# OpAmp.net
KiCad netlist of a schematic drawn in Altium Designer
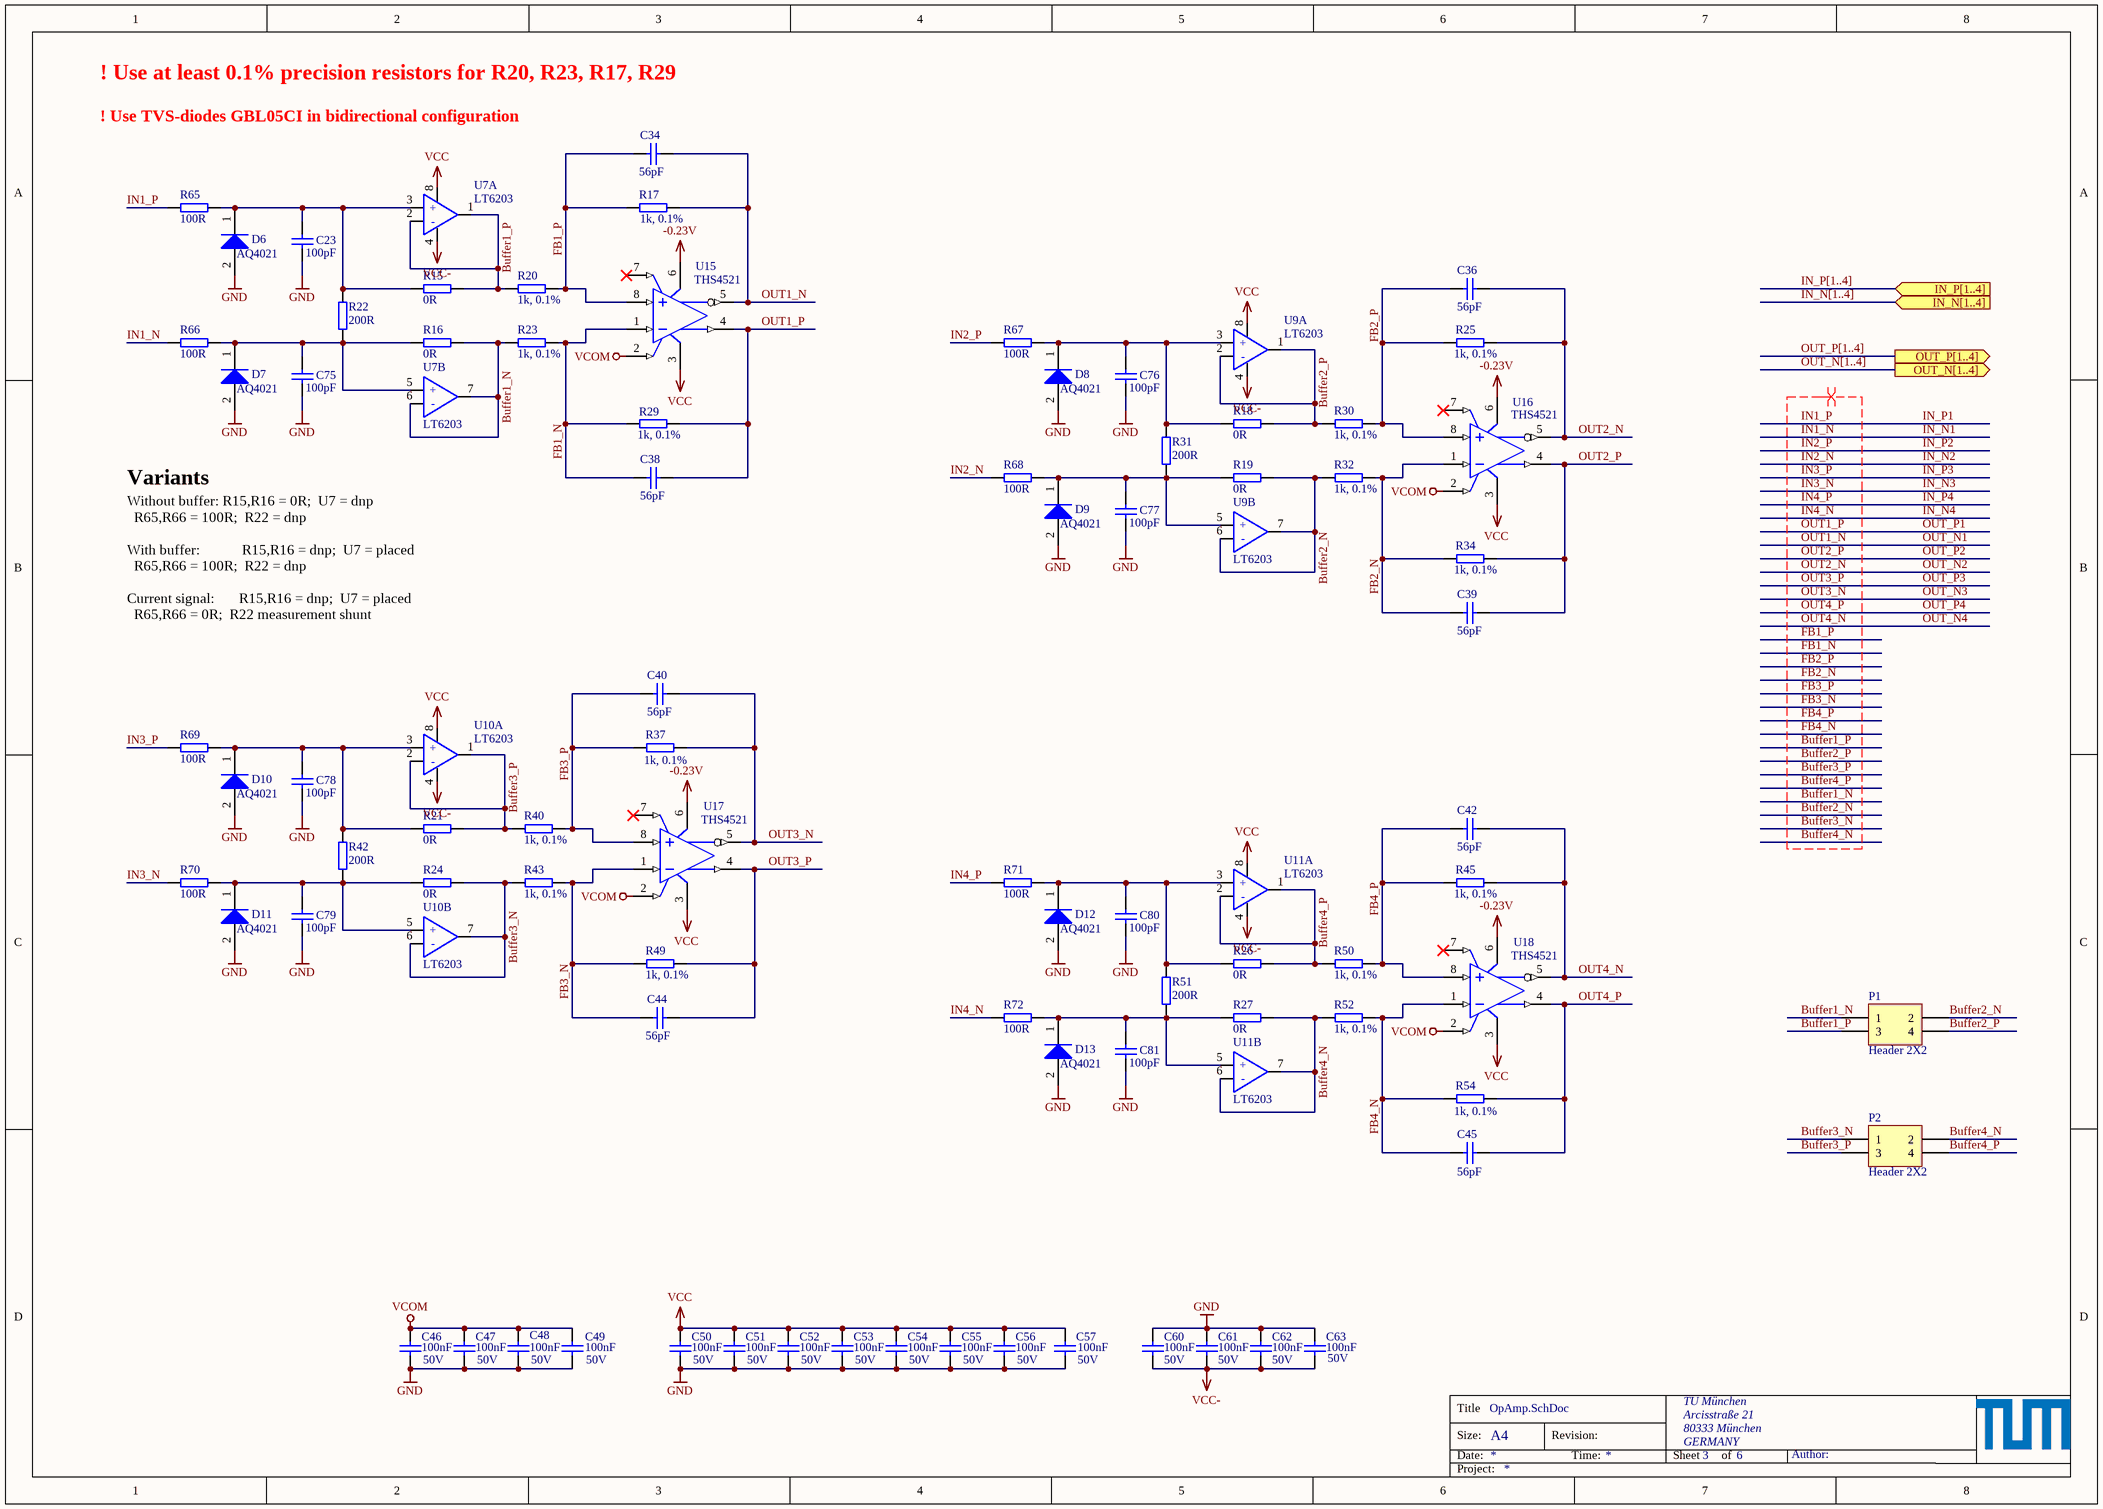
[diagram p0: OpAmp.SchDoc]

(export (version "E")
  (design (tool "Eeschema 10.0.6"))
  (components
    (comp (ref "C23")
      (value "100pF")
      (footprint "CAPC1608X07N")
      (fields
        (field (name "MF") "Würth Elektronik")
        (field (name "MPN") "885012006057")
        (field (name "VOLTAGE") "50V")
      )
      (libsource (lib "UltraZohm_ADC") (part "Cap_0603"))
    )
    (comp (ref "C34")
      (value "56pF")
      (footprint "CAPC1608X07N")
      (fields
        (field (name "MF") "Vishay")
        (field (name "MPN") "VJ0603A560JXACW1BC")
        (field (name "VOLTAGE") "50V")
      )
      (libsource (lib "UltraZohm_ADC") (part "Cap_0603"))
    )
    (comp (ref "C36")
      (value "56pF")
      (footprint "CAPC1608X07N")
      (fields
        (field (name "MF") "Vishay")
        (field (name "MPN") "VJ0603A560JXACW1BC")
        (field (name "VOLTAGE") "50V")
      )
      (libsource (lib "UltraZohm_ADC") (part "Cap_0603"))
    )
    (comp (ref "C38")
      (value "56pF")
      (footprint "CAPC1608X07N")
      (fields
        (field (name "MF") "Vishay")
        (field (name "MPN") "VJ0603A560JXACW1BC")
        (field (name "VOLTAGE") "50V")
      )
      (libsource (lib "UltraZohm_ADC") (part "Cap_0603"))
    )
    (comp (ref "C39")
      (value "56pF")
      (footprint "CAPC1608X07N")
      (fields
        (field (name "MF") "Vishay")
        (field (name "MPN") "VJ0603A560JXACW1BC")
        (field (name "VOLTAGE") "50V")
      )
      (libsource (lib "UltraZohm_ADC") (part "Cap_0603"))
    )
    (comp (ref "C40")
      (value "56pF")
      (footprint "CAPC1608X07N")
      (fields
        (field (name "MF") "Vishay")
        (field (name "MPN") "VJ0603A560JXACW1BC")
        (field (name "VOLTAGE") "50V")
      )
      (libsource (lib "UltraZohm_ADC") (part "Cap_0603"))
    )
    (comp (ref "C42")
      (value "56pF")
      (footprint "CAPC1608X07N")
      (fields
        (field (name "MF") "Vishay")
        (field (name "MPN") "VJ0603A560JXACW1BC")
        (field (name "VOLTAGE") "50V")
      )
      (libsource (lib "UltraZohm_ADC") (part "Cap_0603"))
    )
    (comp (ref "C44")
      (value "56pF")
      (footprint "CAPC1608X07N")
      (fields
        (field (name "MF") "Vishay")
        (field (name "MPN") "VJ0603A560JXACW1BC")
        (field (name "VOLTAGE") "50V")
      )
      (libsource (lib "UltraZohm_ADC") (part "Cap_0603"))
    )
    (comp (ref "C45")
      (value "56pF")
      (footprint "CAPC1608X07N")
      (fields
        (field (name "MF") "Vishay")
        (field (name "MPN") "VJ0603A560JXACW1BC")
        (field (name "VOLTAGE") "50V")
      )
      (libsource (lib "UltraZohm_ADC") (part "Cap_0603"))
    )
    (comp (ref "C46")
      (value "100nF")
      (footprint "CAPC1608X07N")
      (fields
        (field (name "MF") "Yageo")
        (field (name "MPN") "CC0603KRX7R9BB104")
        (field (name "VOLTAGE") "50V")
      )
      (libsource (lib "UltraZohm_ADC") (part "Cap_0603"))
    )
    (comp (ref "C47")
      (value "100nF")
      (footprint "CAPC1608X07N")
      (fields
        (field (name "MF") "Yageo")
        (field (name "MPN") "CC0603KRX7R9BB104")
        (field (name "VOLTAGE") "50V")
      )
      (libsource (lib "UltraZohm_ADC") (part "Cap_0603"))
    )
    (comp (ref "C48")
      (value "100nF")
      (footprint "CAPC1608X07N")
      (fields
        (field (name "MF") "Yageo")
        (field (name "MPN") "CC0603KRX7R9BB104")
        (field (name "VOLTAGE") "50V")
      )
      (libsource (lib "UltraZohm_ADC") (part "Cap_0603"))
    )
    (comp (ref "C49")
      (value "100nF")
      (footprint "CAPC1608X07N")
      (fields
        (field (name "MF") "Yageo")
        (field (name "MPN") "CC0603KRX7R9BB104")
        (field (name "VOLTAGE") "50V")
      )
      (libsource (lib "UltraZohm_ADC") (part "Cap_0603"))
    )
    (comp (ref "C50")
      (value "100nF")
      (footprint "CAPC1608X07N")
      (fields
        (field (name "MF") "Yageo")
        (field (name "MPN") "CC0603KRX7R9BB104")
        (field (name "VOLTAGE") "50V")
      )
      (libsource (lib "UltraZohm_ADC") (part "Cap_0603"))
    )
    (comp (ref "C51")
      (value "100nF")
      (footprint "CAPC1608X07N")
      (fields
        (field (name "MF") "Yageo")
        (field (name "MPN") "CC0603KRX7R9BB104")
        (field (name "VOLTAGE") "50V")
      )
      (libsource (lib "UltraZohm_ADC") (part "Cap_0603"))
    )
    (comp (ref "C52")
      (value "100nF")
      (footprint "CAPC1608X07N")
      (fields
        (field (name "MF") "Yageo")
        (field (name "MPN") "CC0603KRX7R9BB104")
        (field (name "VOLTAGE") "50V")
      )
      (libsource (lib "UltraZohm_ADC") (part "Cap_0603"))
    )
    (comp (ref "C53")
      (value "100nF")
      (footprint "CAPC1608X07N")
      (fields
        (field (name "MF") "Yageo")
        (field (name "MPN") "CC0603KRX7R9BB104")
        (field (name "VOLTAGE") "50V")
      )
      (libsource (lib "UltraZohm_ADC") (part "Cap_0603"))
    )
    (comp (ref "C54")
      (value "100nF")
      (footprint "CAPC1608X07N")
      (fields
        (field (name "MF") "Yageo")
        (field (name "MPN") "CC0603KRX7R9BB104")
        (field (name "VOLTAGE") "50V")
      )
      (libsource (lib "UltraZohm_ADC") (part "Cap_0603"))
    )
    (comp (ref "C55")
      (value "100nF")
      (footprint "CAPC1608X07N")
      (fields
        (field (name "MF") "Yageo")
        (field (name "MPN") "CC0603KRX7R9BB104")
        (field (name "VOLTAGE") "50V")
      )
      (libsource (lib "UltraZohm_ADC") (part "Cap_0603"))
    )
    (comp (ref "C56")
      (value "100nF")
      (footprint "CAPC1608X07N")
      (fields
        (field (name "MF") "Yageo")
        (field (name "MPN") "CC0603KRX7R9BB104")
        (field (name "VOLTAGE") "50V")
      )
      (libsource (lib "UltraZohm_ADC") (part "Cap_0603"))
    )
    (comp (ref "C57")
      (value "100nF")
      (footprint "CAPC1608X07N")
      (fields
        (field (name "MF") "Yageo")
        (field (name "MPN") "CC0603KRX7R9BB104")
        (field (name "VOLTAGE") "50V")
      )
      (libsource (lib "UltraZohm_ADC") (part "Cap_0603"))
    )
    (comp (ref "C60")
      (value "100nF")
      (footprint "CAPC1608X07N")
      (fields
        (field (name "MF") "Yageo")
        (field (name "MPN") "CC0603KRX7R9BB104")
        (field (name "VOLTAGE") "50V")
      )
      (libsource (lib "UltraZohm_ADC") (part "Cap_0603"))
    )
    (comp (ref "C61")
      (value "100nF")
      (footprint "CAPC1608X07N")
      (fields
        (field (name "MF") "Yageo")
        (field (name "MPN") "CC0603KRX7R9BB104")
        (field (name "VOLTAGE") "50V")
      )
      (libsource (lib "UltraZohm_ADC") (part "Cap_0603"))
    )
    (comp (ref "C62")
      (value "100nF")
      (footprint "CAPC1608X07N")
      (fields
        (field (name "MF") "Yageo")
        (field (name "MPN") "CC0603KRX7R9BB104")
        (field (name "VOLTAGE") "50V")
      )
      (libsource (lib "UltraZohm_ADC") (part "Cap_0603"))
    )
    (comp (ref "C63")
      (value "100nF")
      (footprint "CAPC1608X07N")
      (fields
        (field (name "MF") "Yageo")
        (field (name "MPN") "CC0603KRX7R9BB104")
        (field (name "VOLTAGE") "50V")
      )
      (libsource (lib "UltraZohm_ADC") (part "Cap_0603"))
    )
    (comp (ref "C75")
      (value "100pF")
      (footprint "CAPC1608X07N")
      (fields
        (field (name "MF") "Würth Elektronik")
        (field (name "MPN") "885012006057")
        (field (name "VOLTAGE") "50V")
      )
      (libsource (lib "UltraZohm_ADC") (part "Cap_0603"))
    )
    (comp (ref "C76")
      (value "100pF")
      (footprint "CAPC1608X07N")
      (fields
        (field (name "MF") "Würth Elektronik")
        (field (name "MPN") "885012006057")
        (field (name "VOLTAGE") "50V")
      )
      (libsource (lib "UltraZohm_ADC") (part "Cap_0603"))
    )
    (comp (ref "C77")
      (value "100pF")
      (footprint "CAPC1608X07N")
      (fields
        (field (name "MF") "Würth Elektronik")
        (field (name "MPN") "885012006057")
        (field (name "VOLTAGE") "50V")
      )
      (libsource (lib "UltraZohm_ADC") (part "Cap_0603"))
    )
    (comp (ref "C78")
      (value "100pF")
      (footprint "CAPC1608X07N")
      (fields
        (field (name "MF") "Würth Elektronik")
        (field (name "MPN") "885012006057")
        (field (name "VOLTAGE") "50V")
      )
      (libsource (lib "UltraZohm_ADC") (part "Cap_0603"))
    )
    (comp (ref "C79")
      (value "100pF")
      (footprint "CAPC1608X07N")
      (fields
        (field (name "MF") "Würth Elektronik")
        (field (name "MPN") "885012006057")
        (field (name "VOLTAGE") "50V")
      )
      (libsource (lib "UltraZohm_ADC") (part "Cap_0603"))
    )
    (comp (ref "C80")
      (value "100pF")
      (footprint "CAPC1608X07N")
      (fields
        (field (name "MF") "Würth Elektronik")
        (field (name "MPN") "885012006057")
        (field (name "VOLTAGE") "50V")
      )
      (libsource (lib "UltraZohm_ADC") (part "Cap_0603"))
    )
    (comp (ref "C81")
      (value "100pF")
      (footprint "CAPC1608X07N")
      (fields
        (field (name "MF") "Würth Elektronik")
        (field (name "MPN") "885012006057")
        (field (name "VOLTAGE") "50V")
      )
      (libsource (lib "UltraZohm_ADC") (part "Cap_0603"))
    )
    (comp (ref "D6")
      (value "AQ4021")
      (footprint "SOD-323_SuppressorDiode")
      (description "ESD Suppressor Diode TVS Bi-Dir 5V")
      (fields (field (name "MF") "Littelfuse") (field (name "MPN") "AQ4021-01FTG-C"))
      (libsource (lib "UltraZohm_ADC") (part "GBLCxx"))
    )
    (comp (ref "D7")
      (value "AQ4021")
      (footprint "SOD-323_SuppressorDiode")
      (description "ESD Suppressor Diode TVS Bi-Dir 5V")
      (fields (field (name "MF") "Littelfuse") (field (name "MPN") "AQ4021-01FTG-C"))
      (libsource (lib "UltraZohm_ADC") (part "GBLCxx"))
    )
    (comp (ref "D8")
      (value "AQ4021")
      (footprint "SOD-323_SuppressorDiode")
      (description "ESD Suppressor Diode TVS Bi-Dir 5V")
      (fields (field (name "MF") "Littelfuse") (field (name "MPN") "AQ4021-01FTG-C"))
      (libsource (lib "UltraZohm_ADC") (part "GBLCxx"))
    )
    (comp (ref "D9")
      (value "AQ4021")
      (footprint "SOD-323_SuppressorDiode")
      (description "ESD Suppressor Diode TVS Bi-Dir 5V")
      (fields (field (name "MF") "Littelfuse") (field (name "MPN") "AQ4021-01FTG-C"))
      (libsource (lib "UltraZohm_ADC") (part "GBLCxx"))
    )
    (comp (ref "D10")
      (value "AQ4021")
      (footprint "SOD-323_SuppressorDiode")
      (description "ESD Suppressor Diode TVS Bi-Dir 5V")
      (fields (field (name "MF") "Littelfuse") (field (name "MPN") "AQ4021-01FTG-C"))
      (libsource (lib "UltraZohm_ADC") (part "GBLCxx"))
    )
    (comp (ref "D11")
      (value "AQ4021")
      (footprint "SOD-323_SuppressorDiode")
      (description "ESD Suppressor Diode TVS Bi-Dir 5V")
      (fields (field (name "MF") "Littelfuse") (field (name "MPN") "AQ4021-01FTG-C"))
      (libsource (lib "UltraZohm_ADC") (part "GBLCxx"))
    )
    (comp (ref "D12")
      (value "AQ4021")
      (footprint "SOD-323_SuppressorDiode")
      (description "ESD Suppressor Diode TVS Bi-Dir 5V")
      (fields (field (name "MF") "Littelfuse") (field (name "MPN") "AQ4021-01FTG-C"))
      (libsource (lib "UltraZohm_ADC") (part "GBLCxx"))
    )
    (comp (ref "D13")
      (value "AQ4021")
      (footprint "SOD-323_SuppressorDiode")
      (description "ESD Suppressor Diode TVS Bi-Dir 5V")
      (fields (field (name "MF") "Littelfuse") (field (name "MPN") "AQ4021-01FTG-C"))
      (libsource (lib "UltraZohm_ADC") (part "GBLCxx"))
    )
    (comp (ref "P1")
      (value "Header 2X2")
      (footprint "HDR2X2")
      (description "Header, 2-Pin, Dual row")
      (fields (field (name "PUBLISHER") "Altium Limited"))
      (libsource (lib "Miscellaneous Connectors") (part "Header 2X2"))
    )
    (comp (ref "P2")
      (value "Header 2X2")
      (footprint "HDR2X2")
      (description "Header, 2-Pin, Dual row")
      (fields (field (name "PUBLISHER") "Altium Limited"))
      (libsource (lib "Miscellaneous Connectors") (part "Header 2X2"))
    )
    (comp (ref "R15")
      (value "0R")
      (footprint "RESC1608X06N")
      (fields (field (name "MF") "Vishay / Dale") (field (name "MPN") "CRCW06030000Z0EBC"))
      (libsource (lib "UltraZohm_ADC") (part "R_0603"))
    )
    (comp (ref "R16")
      (value "0R")
      (footprint "RESC1608X06N")
      (fields (field (name "MF") "Vishay / Dale") (field (name "MPN") "CRCW06030000Z0EBC"))
      (libsource (lib "UltraZohm_ADC") (part "R_0603"))
    )
    (comp (ref "R17")
      (value "1k, 0.1%")
      (footprint "RESC1608X06N")
      (description "Precision Resistor 1k 0.1% 0603")
      (fields (field (name "MF") "IRC/TT Electronics") (field (name "MPN") "PCF-W0603LF-03-1001-B-P-LT"))
      (libsource (lib "UltraZohm_ADC") (part "R_0603"))
    )
    (comp (ref "R18")
      (value "0R")
      (footprint "RESC1608X06N")
      (fields (field (name "MF") "Vishay / Dale") (field (name "MPN") "CRCW06030000Z0EBC"))
      (libsource (lib "UltraZohm_ADC") (part "R_0603"))
    )
    (comp (ref "R19")
      (value "0R")
      (footprint "RESC1608X06N")
      (fields (field (name "MF") "Vishay / Dale") (field (name "MPN") "CRCW06030000Z0EBC"))
      (libsource (lib "UltraZohm_ADC") (part "R_0603"))
    )
    (comp (ref "R20")
      (value "1k, 0.1%")
      (footprint "RESC1608X06N")
      (description "Precision Resistor 1k 0.1% 0603")
      (fields (field (name "MF") "IRC/TT Electronics") (field (name "MPN") "PCF-W0603LF-03-1001-B-P-LT"))
      (libsource (lib "UltraZohm_ADC") (part "R_0603"))
    )
    (comp (ref "R21")
      (value "0R")
      (footprint "RESC1608X06N")
      (fields (field (name "MF") "Vishay / Dale") (field (name "MPN") "CRCW06030000Z0EBC"))
      (libsource (lib "UltraZohm_ADC") (part "R_0603"))
    )
    (comp (ref "R22")
      (value "200R")
      (footprint "RESC3216X65N")
      (description "WID SMD 1M 5% 0,25W")
      (fields
        (field (name "TOLERANCE") "5%")
        (field (name "MF") "AECOL/Ohmite")
        (field (name "CREATED") "2018_07_20_AGeiger")
      )
      (libsource (lib "UltraZOhm_CarrierBoard") (part "R_1206"))
    )
    (comp (ref "R23")
      (value "1k, 0.1%")
      (footprint "RESC1608X06N")
      (description "Precision Resistor 1k 0.1% 0603")
      (fields (field (name "MF") "IRC/TT Electronics") (field (name "MPN") "PCF-W0603LF-03-1001-B-P-LT"))
      (libsource (lib "UltraZohm_ADC") (part "R_0603"))
    )
    (comp (ref "R24")
      (value "0R")
      (footprint "RESC1608X06N")
      (fields (field (name "MF") "Vishay / Dale") (field (name "MPN") "CRCW06030000Z0EBC"))
      (libsource (lib "UltraZohm_ADC") (part "R_0603"))
    )
    (comp (ref "R25")
      (value "1k, 0.1%")
      (footprint "RESC1608X06N")
      (description "Precision Resistor 1k 0.1% 0603")
      (fields (field (name "MF") "IRC/TT Electronics") (field (name "MPN") "PCF-W0603LF-03-1001-B-P-LT"))
      (libsource (lib "UltraZohm_ADC") (part "R_0603"))
    )
    (comp (ref "R26")
      (value "0R")
      (footprint "RESC1608X06N")
      (fields (field (name "MF") "Vishay / Dale") (field (name "MPN") "CRCW06030000Z0EBC"))
      (libsource (lib "UltraZohm_ADC") (part "R_0603"))
    )
    (comp (ref "R27")
      (value "0R")
      (footprint "RESC1608X06N")
      (fields (field (name "MF") "Vishay / Dale") (field (name "MPN") "CRCW06030000Z0EBC"))
      (libsource (lib "UltraZohm_ADC") (part "R_0603"))
    )
    (comp (ref "R29")
      (value "1k, 0.1%")
      (footprint "RESC1608X06N")
      (description "Precision Resistor 1k 0.1% 0603")
      (fields (field (name "MF") "IRC/TT Electronics") (field (name "MPN") "PCF-W0603LF-03-1001-B-P-LT"))
      (libsource (lib "UltraZohm_ADC") (part "R_0603"))
    )
    (comp (ref "R30")
      (value "1k, 0.1%")
      (footprint "RESC1608X06N")
      (description "Precision Resistor 1k 0.1% 0603")
      (fields (field (name "MF") "IRC/TT Electronics") (field (name "MPN") "PCF-W0603LF-03-1001-B-P-LT"))
      (libsource (lib "UltraZohm_ADC") (part "R_0603"))
    )
    (comp (ref "R31")
      (value "200R")
      (footprint "RESC3216X65N")
      (description "WID SMD 1M 5% 0,25W")
      (fields
        (field (name "TOLERANCE") "5%")
        (field (name "MF") "AECOL/Ohmite")
        (field (name "CREATED") "2018_07_20_AGeiger")
      )
      (libsource (lib "UltraZOhm_CarrierBoard") (part "R_1206"))
    )
    (comp (ref "R32")
      (value "1k, 0.1%")
      (footprint "RESC1608X06N")
      (description "Precision Resistor 1k 0.1% 0603")
      (fields (field (name "MF") "IRC/TT Electronics") (field (name "MPN") "PCF-W0603LF-03-1001-B-P-LT"))
      (libsource (lib "UltraZohm_ADC") (part "R_0603"))
    )
    (comp (ref "R34")
      (value "1k, 0.1%")
      (footprint "RESC1608X06N")
      (description "Precision Resistor 1k 0.1% 0603")
      (fields (field (name "MF") "IRC/TT Electronics") (field (name "MPN") "PCF-W0603LF-03-1001-B-P-LT"))
      (libsource (lib "UltraZohm_ADC") (part "R_0603"))
    )
    (comp (ref "R37")
      (value "1k, 0.1%")
      (footprint "RESC1608X06N")
      (description "Precision Resistor 1k 0.1% 0603")
      (fields (field (name "MF") "IRC/TT Electronics") (field (name "MPN") "PCF-W0603LF-03-1001-B-P-LT"))
      (libsource (lib "UltraZohm_ADC") (part "R_0603"))
    )
    (comp (ref "R40")
      (value "1k, 0.1%")
      (footprint "RESC1608X06N")
      (description "Precision Resistor 1k 0.1% 0603")
      (fields (field (name "MF") "IRC/TT Electronics") (field (name "MPN") "PCF-W0603LF-03-1001-B-P-LT"))
      (libsource (lib "UltraZohm_ADC") (part "R_0603"))
    )
    (comp (ref "R42")
      (value "200R")
      (footprint "RESC3216X65N")
      (description "WID SMD 1M 5% 0,25W")
      (fields
        (field (name "TOLERANCE") "5%")
        (field (name "MF") "AECOL/Ohmite")
        (field (name "CREATED") "2018_07_20_AGeiger")
      )
      (libsource (lib "UltraZOhm_CarrierBoard") (part "R_1206"))
    )
    (comp (ref "R43")
      (value "1k, 0.1%")
      (footprint "RESC1608X06N")
      (description "Precision Resistor 1k 0.1% 0603")
      (fields (field (name "MF") "IRC/TT Electronics") (field (name "MPN") "PCF-W0603LF-03-1001-B-P-LT"))
      (libsource (lib "UltraZohm_ADC") (part "R_0805"))
    )
    (comp (ref "R45")
      (value "1k, 0.1%")
      (footprint "RESC1608X06N")
      (description "Precision Resistor 1k 0.1% 0603")
      (fields (field (name "MF") "IRC/TT Electronics") (field (name "MPN") "PCF-W0603LF-03-1001-B-P-LT"))
      (libsource (lib "UltraZohm_ADC") (part "R_0603"))
    )
    (comp (ref "R49")
      (value "1k, 0.1%")
      (footprint "RESC1608X06N")
      (description "Precision Resistor 1k 0.1% 0603")
      (fields (field (name "MF") "IRC/TT Electronics") (field (name "MPN") "PCF-W0603LF-03-1001-B-P-LT"))
      (libsource (lib "UltraZohm_ADC") (part "R_0603"))
    )
    (comp (ref "R50")
      (value "1k, 0.1%")
      (footprint "RESC1608X06N")
      (description "Precision Resistor 1k 0.1% 0603")
      (fields (field (name "MF") "IRC/TT Electronics") (field (name "MPN") "PCF-W0603LF-03-1001-B-P-LT"))
      (libsource (lib "UltraZohm_ADC") (part "R_0603"))
    )
    (comp (ref "R51")
      (value "200R")
      (footprint "RESC3216X65N")
      (description "WID SMD 1M 5% 0,25W")
      (fields
        (field (name "TOLERANCE") "5%")
        (field (name "MF") "AECOL/Ohmite")
        (field (name "CREATED") "2018_07_20_AGeiger")
      )
      (libsource (lib "UltraZOhm_CarrierBoard") (part "R_1206"))
    )
    (comp (ref "R52")
      (value "1k, 0.1%")
      (footprint "RESC1608X06N")
      (description "Precision Resistor 1k 0.1% 0603")
      (fields (field (name "MF") "IRC/TT Electronics") (field (name "MPN") "PCF-W0603LF-03-1001-B-P-LT"))
      (libsource (lib "UltraZohm_ADC") (part "R_0603"))
    )
    (comp (ref "R54")
      (value "1k, 0.1%")
      (footprint "RESC1608X06N")
      (description "Precision Resistor 1k 0.1% 0603")
      (fields (field (name "MF") "IRC/TT Electronics") (field (name "MPN") "PCF-W0603LF-03-1001-B-P-LT"))
      (libsource (lib "UltraZohm_ADC") (part "R_0603"))
    )
    (comp (ref "R65")
      (value "100R")
      (footprint "RESC1608X06N")
      (fields
        (field (name "MF") "Yageo")
        (field (name "MPN") "AC0603FR-13100RL")
        (field (name "TOLERANCE") "1%")
      )
      (libsource (lib "UltraZohm_ADC") (part "R_0603"))
    )
    (comp (ref "R66")
      (value "100R")
      (footprint "RESC1608X06N")
      (fields
        (field (name "MF") "Yageo")
        (field (name "MPN") "AC0603FR-13100RL")
        (field (name "TOLERANCE") "1%")
      )
      (libsource (lib "UltraZohm_ADC") (part "R_0603"))
    )
    (comp (ref "R67")
      (value "100R")
      (footprint "RESC1608X06N")
      (fields
        (field (name "MF") "Yageo")
        (field (name "MPN") "AC0603FR-13100RL")
        (field (name "TOLERANCE") "1%")
      )
      (libsource (lib "UltraZohm_ADC") (part "R_0603"))
    )
    (comp (ref "R68")
      (value "100R")
      (footprint "RESC1608X06N")
      (fields
        (field (name "MF") "Yageo")
        (field (name "MPN") "AC0603FR-13100RL")
        (field (name "TOLERANCE") "1%")
      )
      (libsource (lib "UltraZohm_ADC") (part "R_0603"))
    )
    (comp (ref "R69")
      (value "100R")
      (footprint "RESC1608X06N")
      (fields
        (field (name "MF") "Yageo")
        (field (name "MPN") "AC0603FR-13100RL")
        (field (name "TOLERANCE") "1%")
      )
      (libsource (lib "UltraZohm_ADC") (part "R_0603"))
    )
    (comp (ref "R70")
      (value "100R")
      (footprint "RESC1608X06N")
      (fields
        (field (name "MF") "Yageo")
        (field (name "MPN") "AC0603FR-13100RL")
        (field (name "TOLERANCE") "1%")
      )
      (libsource (lib "UltraZohm_ADC") (part "R_0603"))
    )
    (comp (ref "R71")
      (value "100R")
      (footprint "RESC1608X06N")
      (fields
        (field (name "MF") "Yageo")
        (field (name "MPN") "AC0603FR-13100RL")
        (field (name "TOLERANCE") "1%")
      )
      (libsource (lib "UltraZohm_ADC") (part "R_0603"))
    )
    (comp (ref "R72")
      (value "100R")
      (footprint "RESC1608X06N")
      (fields
        (field (name "MF") "Yageo")
        (field (name "MPN") "AC0603FR-13100RL")
        (field (name "TOLERANCE") "1%")
      )
      (libsource (lib "UltraZohm_ADC") (part "R_0603"))
    )
    (comp (ref "U7")
      (value "LT6203")
      (footprint "MSOP8_3x3-8N")
      (description "2 Ch Low Noise, Low Power OpAmp")
      (fields
        (field (name "MF") "Linear Technology")
        (field (name "MPN") "LT6203CMS8#PBF")
        (field (name "CREATED") "Kreppel_20190830")
      )
      (libsource (lib "UltraZohm_ADC") (part "LT6203_MSOP8"))
    )
    (comp (ref "U9")
      (value "LT6203")
      (footprint "MSOP8_3x3-8N")
      (description "2 Ch Low Noise, Low Power OpAmp")
      (fields
        (field (name "MF") "Linear Technology")
        (field (name "MPN") "LT6203CMS8#PBF")
        (field (name "CREATED") "Kreppel_20190830")
      )
      (libsource (lib "UltraZohm_ADC") (part "LT6203_MSOP8"))
    )
    (comp (ref "U10")
      (value "LT6203")
      (footprint "MSOP8_3x3-8N")
      (description "2 Ch Low Noise, Low Power OpAmp")
      (fields
        (field (name "MF") "Linear Technology")
        (field (name "MPN") "LT6203CMS8#PBF")
        (field (name "CREATED") "Kreppel_20190830")
      )
      (libsource (lib "UltraZohm_ADC") (part "LT6203_MSOP8"))
    )
    (comp (ref "U11")
      (value "LT6203")
      (footprint "MSOP8_3x3-8N")
      (description "2 Ch Low Noise, Low Power OpAmp")
      (fields
        (field (name "MF") "Linear Technology")
        (field (name "MPN") "LT6203CMS8#PBF")
        (field (name "CREATED") "Kreppel_20190830")
      )
      (libsource (lib "UltraZohm_ADC") (part "LT6203_MSOP8"))
    )
    (comp (ref "U15")
      (value "THS4521")
      (footprint "DGK0008A_N")
      (description "IC AMP RRO NEG OUT VLP 8VSSOP (Single Channel fully differential Amplifier)")
      (fields
        (field (name "MANUFACTURER") "Texas Instruments")
        (field (name "MANUFACTURER PART NUMBER") "THS4521IDGKR")
      )
      (libsource (lib "UltraZohm_ADC") (part "THS4521IDGKR"))
    )
    (comp (ref "U16")
      (value "THS4521")
      (footprint "DGK0008A_N")
      (description "IC AMP RRO NEG OUT VLP 8VSSOP (Single Channel fully differential Amplifier)")
      (fields
        (field (name "MANUFACTURER") "Texas Instruments")
        (field (name "MANUFACTURER PART NUMBER") "THS4521IDGKR")
      )
      (libsource (lib "UltraZohm_ADC") (part "THS4521IDGKR"))
    )
    (comp (ref "U17")
      (value "THS4521")
      (footprint "DGK0008A_N")
      (description "IC AMP RRO NEG OUT VLP 8VSSOP (Single Channel fully differential Amplifier)")
      (fields
        (field (name "MANUFACTURER") "Texas Instruments")
        (field (name "MANUFACTURER PART NUMBER") "THS4521IDGKR")
      )
      (libsource (lib "UltraZohm_ADC") (part "THS4521IDGKR"))
    )
    (comp (ref "U18")
      (value "THS4521")
      (footprint "DGK0008A_N")
      (description "IC AMP RRO NEG OUT VLP 8VSSOP (Single Channel fully differential Amplifier)")
      (fields
        (field (name "MANUFACTURER") "Texas Instruments")
        (field (name "MANUFACTURER PART NUMBER") "THS4521IDGKR")
      )
      (libsource (lib "UltraZohm_ADC") (part "THS4521IDGKR"))
    )
  )
  (nets
    (net (code "1") (name "-0.23V") (class "Default")
      (node (ref "U15") (pin "6") (pinfunction "VS-_6") (pintype "power_in"))
      (node (ref "U16") (pin "6") (pinfunction "VS-_6") (pintype "power_in"))
      (node (ref "U17") (pin "6") (pinfunction "VS-_6") (pintype "power_in"))
      (node (ref "U18") (pin "6") (pinfunction "VS-_6") (pintype "power_in"))
    )
    (net (code "2") (name "/Buffer1_N") (class "Default")
      (node (ref "P1") (pin "1") (pinfunction "1_1") (pintype "passive"))
      (node (ref "R16") (pin "2") (pintype "passive"))
      (node (ref "R23") (pin "2") (pintype "passive"))
      (node (ref "U7") (pin "6") (pinfunction "-_6") (pintype "passive"))
      (node (ref "U7") (pin "7") (pintype "passive"))
    )
    (net (code "3") (name "/Buffer1_P") (class "Default")
      (node (ref "P1") (pin "3") (pinfunction "3_3") (pintype "passive"))
      (node (ref "R15") (pin "2") (pintype "passive"))
      (node (ref "R20") (pin "1") (pintype "passive"))
      (node (ref "U7") (pin "1") (pintype "passive"))
      (node (ref "U7") (pin "2") (pinfunction "-_2") (pintype "passive"))
    )
    (net (code "4") (name "/Buffer2_N") (class "Default")
      (node (ref "P1") (pin "2") (pinfunction "2_2") (pintype "passive"))
      (node (ref "R19") (pin "2") (pintype "passive"))
      (node (ref "R32") (pin "2") (pintype "passive"))
      (node (ref "U9") (pin "6") (pinfunction "-_6") (pintype "passive"))
      (node (ref "U9") (pin "7") (pintype "passive"))
    )
    (net (code "5") (name "/Buffer2_P") (class "Default")
      (node (ref "P1") (pin "4") (pinfunction "4_4") (pintype "passive"))
      (node (ref "R18") (pin "2") (pintype "passive"))
      (node (ref "R30") (pin "1") (pintype "passive"))
      (node (ref "U9") (pin "1") (pintype "passive"))
      (node (ref "U9") (pin "2") (pinfunction "-_2") (pintype "passive"))
    )
    (net (code "6") (name "/Buffer3_N") (class "Default")
      (node (ref "P2") (pin "1") (pinfunction "1_1") (pintype "passive"))
      (node (ref "R24") (pin "2") (pintype "passive"))
      (node (ref "R43") (pin "2") (pintype "passive"))
      (node (ref "U10") (pin "6") (pinfunction "-_6") (pintype "passive"))
      (node (ref "U10") (pin "7") (pintype "passive"))
    )
    (net (code "7") (name "/Buffer3_P") (class "Default")
      (node (ref "P2") (pin "3") (pinfunction "3_3") (pintype "passive"))
      (node (ref "R21") (pin "2") (pintype "passive"))
      (node (ref "R40") (pin "1") (pintype "passive"))
      (node (ref "U10") (pin "1") (pintype "passive"))
      (node (ref "U10") (pin "2") (pinfunction "-_2") (pintype "passive"))
    )
    (net (code "8") (name "/Buffer4_N") (class "Default")
      (node (ref "P2") (pin "2") (pinfunction "2_2") (pintype "passive"))
      (node (ref "R27") (pin "2") (pintype "passive"))
      (node (ref "R52") (pin "2") (pintype "passive"))
      (node (ref "U11") (pin "6") (pinfunction "-_6") (pintype "passive"))
      (node (ref "U11") (pin "7") (pintype "passive"))
    )
    (net (code "9") (name "/Buffer4_P") (class "Default")
      (node (ref "P2") (pin "4") (pinfunction "4_4") (pintype "passive"))
      (node (ref "R26") (pin "2") (pintype "passive"))
      (node (ref "R50") (pin "1") (pintype "passive"))
      (node (ref "U11") (pin "1") (pintype "passive"))
      (node (ref "U11") (pin "2") (pinfunction "-_2") (pintype "passive"))
    )
    (net (code "10") (name "/FB1_N") (class "Default")
      (node (ref "C38") (pin "1") (pinfunction "1_1") (pintype "passive"))
      (node (ref "R23") (pin "1") (pintype "passive"))
      (node (ref "R29") (pin "1") (pintype "passive"))
      (node (ref "U15") (pin "1") (pinfunction "VIN-_1") (pintype "input"))
    )
    (net (code "11") (name "/FB1_P") (class "Default")
      (node (ref "C34") (pin "1") (pinfunction "1_1") (pintype "passive"))
      (node (ref "R17") (pin "1") (pintype "passive"))
      (node (ref "R20") (pin "2") (pintype "passive"))
      (node (ref "U15") (pin "8") (pinfunction "VIN+_8") (pintype "input"))
    )
    (net (code "12") (name "/FB2_N") (class "Default")
      (node (ref "C39") (pin "1") (pinfunction "1_1") (pintype "passive"))
      (node (ref "R32") (pin "1") (pintype "passive"))
      (node (ref "R34") (pin "1") (pintype "passive"))
      (node (ref "U16") (pin "1") (pinfunction "VIN-_1") (pintype "input"))
    )
    (net (code "13") (name "/FB2_P") (class "Default")
      (node (ref "C36") (pin "1") (pinfunction "1_1") (pintype "passive"))
      (node (ref "R25") (pin "1") (pintype "passive"))
      (node (ref "R30") (pin "2") (pintype "passive"))
      (node (ref "U16") (pin "8") (pinfunction "VIN+_8") (pintype "input"))
    )
    (net (code "14") (name "/FB3_N") (class "Default")
      (node (ref "C44") (pin "1") (pinfunction "1_1") (pintype "passive"))
      (node (ref "R43") (pin "1") (pintype "passive"))
      (node (ref "R49") (pin "1") (pintype "passive"))
      (node (ref "U17") (pin "1") (pinfunction "VIN-_1") (pintype "input"))
    )
    (net (code "15") (name "/FB3_P") (class "Default")
      (node (ref "C40") (pin "1") (pinfunction "1_1") (pintype "passive"))
      (node (ref "R37") (pin "1") (pintype "passive"))
      (node (ref "R40") (pin "2") (pintype "passive"))
      (node (ref "U17") (pin "8") (pinfunction "VIN+_8") (pintype "input"))
    )
    (net (code "16") (name "/FB4_N") (class "Default")
      (node (ref "C45") (pin "1") (pinfunction "1_1") (pintype "passive"))
      (node (ref "R52") (pin "1") (pintype "passive"))
      (node (ref "R54") (pin "1") (pintype "passive"))
      (node (ref "U18") (pin "1") (pinfunction "VIN-_1") (pintype "input"))
    )
    (net (code "17") (name "/FB4_P") (class "Default")
      (node (ref "C42") (pin "1") (pinfunction "1_1") (pintype "passive"))
      (node (ref "R45") (pin "1") (pintype "passive"))
      (node (ref "R50") (pin "2") (pintype "passive"))
      (node (ref "U18") (pin "8") (pinfunction "VIN+_8") (pintype "input"))
    )
    (net (code "18") (name "/IN_N1") (class "Default") (node (ref "R66") (pin "1") (pintype "passive")))
    (net (code "19") (name "/IN_N2") (class "Default") (node (ref "R68") (pin "1") (pintype "passive")))
    (net (code "20") (name "/IN_N3") (class "Default") (node (ref "R70") (pin "1") (pintype "passive")))
    (net (code "21") (name "/IN_N4") (class "Default") (node (ref "R72") (pin "1") (pintype "passive")))
    (net (code "23") (name "/IN_P1") (class "Default") (node (ref "R65") (pin "1") (pintype "passive")))
    (net (code "24") (name "/IN_P2") (class "Default") (node (ref "R67") (pin "1") (pintype "passive")))
    (net (code "25") (name "/IN_P3") (class "Default") (node (ref "R69") (pin "1") (pintype "passive")))
    (net (code "26") (name "/IN_P4") (class "Default") (node (ref "R71") (pin "1") (pintype "passive")))
    (net (code "28") (name "/OUT_N1") (class "Default")
      (node (ref "C34") (pin "2") (pinfunction "2_2") (pintype "passive"))
      (node (ref "R17") (pin "2") (pintype "passive"))
      (node (ref "U15") (pin "5") (pinfunction "VOUT-_5") (pintype "output"))
    )
    (net (code "29") (name "/OUT_N2") (class "Default")
      (node (ref "C36") (pin "2") (pinfunction "2_2") (pintype "passive"))
      (node (ref "R25") (pin "2") (pintype "passive"))
      (node (ref "U16") (pin "5") (pinfunction "VOUT-_5") (pintype "output"))
    )
    (net (code "30") (name "/OUT_N3") (class "Default")
      (node (ref "C40") (pin "2") (pinfunction "2_2") (pintype "passive"))
      (node (ref "R37") (pin "2") (pintype "passive"))
      (node (ref "U17") (pin "5") (pinfunction "VOUT-_5") (pintype "output"))
    )
    (net (code "31") (name "/OUT_N4") (class "Default")
      (node (ref "C42") (pin "2") (pinfunction "2_2") (pintype "passive"))
      (node (ref "R45") (pin "2") (pintype "passive"))
      (node (ref "U18") (pin "5") (pinfunction "VOUT-_5") (pintype "output"))
    )
    (net (code "33") (name "/OUT_P1") (class "Default")
      (node (ref "C38") (pin "2") (pinfunction "2_2") (pintype "passive"))
      (node (ref "R29") (pin "2") (pintype "passive"))
      (node (ref "U15") (pin "4") (pinfunction "VOUT+_4") (pintype "output"))
    )
    (net (code "34") (name "/OUT_P2") (class "Default")
      (node (ref "C39") (pin "2") (pinfunction "2_2") (pintype "passive"))
      (node (ref "R34") (pin "2") (pintype "passive"))
      (node (ref "U16") (pin "4") (pinfunction "VOUT+_4") (pintype "output"))
    )
    (net (code "35") (name "/OUT_P3") (class "Default")
      (node (ref "C44") (pin "2") (pinfunction "2_2") (pintype "passive"))
      (node (ref "R49") (pin "2") (pintype "passive"))
      (node (ref "U17") (pin "4") (pinfunction "VOUT+_4") (pintype "output"))
    )
    (net (code "36") (name "/OUT_P4") (class "Default")
      (node (ref "C45") (pin "2") (pinfunction "2_2") (pintype "passive"))
      (node (ref "R54") (pin "2") (pintype "passive"))
      (node (ref "U18") (pin "4") (pinfunction "VOUT+_4") (pintype "output"))
    )
    (net (code "38") (name "GND") (class "Default")
      (node (ref "C23") (pin "2") (pinfunction "2_2") (pintype "passive"))
      (node (ref "C46") (pin "2") (pinfunction "2_2") (pintype "passive"))
      (node (ref "C47") (pin "2") (pinfunction "2_2") (pintype "passive"))
      (node (ref "C48") (pin "2") (pinfunction "2_2") (pintype "passive"))
      (node (ref "C49") (pin "2") (pinfunction "2_2") (pintype "passive"))
      (node (ref "C50") (pin "2") (pinfunction "2_2") (pintype "passive"))
      (node (ref "C51") (pin "2") (pinfunction "2_2") (pintype "passive"))
      (node (ref "C52") (pin "2") (pinfunction "2_2") (pintype "passive"))
      (node (ref "C53") (pin "2") (pinfunction "2_2") (pintype "passive"))
      (node (ref "C54") (pin "2") (pinfunction "2_2") (pintype "passive"))
      (node (ref "C55") (pin "2") (pinfunction "2_2") (pintype "passive"))
      (node (ref "C56") (pin "2") (pinfunction "2_2") (pintype "passive"))
      (node (ref "C57") (pin "2") (pinfunction "2_2") (pintype "passive"))
      (node (ref "C60") (pin "1") (pinfunction "1_1") (pintype "passive"))
      (node (ref "C61") (pin "1") (pinfunction "1_1") (pintype "passive"))
      (node (ref "C62") (pin "1") (pinfunction "1_1") (pintype "passive"))
      (node (ref "C63") (pin "1") (pinfunction "1_1") (pintype "passive"))
      (node (ref "C75") (pin "2") (pinfunction "2_2") (pintype "passive"))
      (node (ref "C76") (pin "2") (pinfunction "2_2") (pintype "passive"))
      (node (ref "C77") (pin "2") (pinfunction "2_2") (pintype "passive"))
      (node (ref "C78") (pin "2") (pinfunction "2_2") (pintype "passive"))
      (node (ref "C79") (pin "2") (pinfunction "2_2") (pintype "passive"))
      (node (ref "C80") (pin "2") (pinfunction "2_2") (pintype "passive"))
      (node (ref "C81") (pin "2") (pinfunction "2_2") (pintype "passive"))
      (node (ref "D10") (pin "2") (pinfunction "A_2") (pintype "passive"))
      (node (ref "D11") (pin "2") (pinfunction "A_2") (pintype "passive"))
      (node (ref "D12") (pin "2") (pinfunction "A_2") (pintype "passive"))
      (node (ref "D13") (pin "2") (pinfunction "A_2") (pintype "passive"))
      (node (ref "D6") (pin "2") (pinfunction "A_2") (pintype "passive"))
      (node (ref "D7") (pin "2") (pinfunction "A_2") (pintype "passive"))
      (node (ref "D8") (pin "2") (pinfunction "A_2") (pintype "passive"))
      (node (ref "D9") (pin "2") (pinfunction "A_2") (pintype "passive"))
    )
    (net (code "39") (name "Net-(D6-K)") (class "Default")
      (node (ref "C23") (pin "1") (pinfunction "1_1") (pintype "passive"))
      (node (ref "D6") (pin "1") (pinfunction "K_1") (pintype "passive"))
      (node (ref "R15") (pin "1") (pintype "passive"))
      (node (ref "R22") (pin "2") (pinfunction "2_2") (pintype "passive"))
      (node (ref "R65") (pin "2") (pintype "passive"))
      (node (ref "U7") (pin "3") (pinfunction "+_3") (pintype "passive"))
    )
    (net (code "40") (name "Net-(D7-K)") (class "Default")
      (node (ref "C75") (pin "1") (pinfunction "1_1") (pintype "passive"))
      (node (ref "D7") (pin "1") (pinfunction "K_1") (pintype "passive"))
      (node (ref "R16") (pin "1") (pintype "passive"))
      (node (ref "R22") (pin "1") (pinfunction "1_1") (pintype "passive"))
      (node (ref "R66") (pin "2") (pintype "passive"))
      (node (ref "U7") (pin "5") (pinfunction "+_5") (pintype "passive"))
    )
    (net (code "41") (name "Net-(D8-K)") (class "Default")
      (node (ref "C76") (pin "1") (pinfunction "1_1") (pintype "passive"))
      (node (ref "D8") (pin "1") (pinfunction "K_1") (pintype "passive"))
      (node (ref "R18") (pin "1") (pintype "passive"))
      (node (ref "R31") (pin "2") (pinfunction "2_2") (pintype "passive"))
      (node (ref "R67") (pin "2") (pintype "passive"))
      (node (ref "U9") (pin "3") (pinfunction "+_3") (pintype "passive"))
    )
    (net (code "42") (name "Net-(D9-K)") (class "Default")
      (node (ref "C77") (pin "1") (pinfunction "1_1") (pintype "passive"))
      (node (ref "D9") (pin "1") (pinfunction "K_1") (pintype "passive"))
      (node (ref "R19") (pin "1") (pintype "passive"))
      (node (ref "R31") (pin "1") (pinfunction "1_1") (pintype "passive"))
      (node (ref "R68") (pin "2") (pintype "passive"))
      (node (ref "U9") (pin "5") (pinfunction "+_5") (pintype "passive"))
    )
    (net (code "43") (name "Net-(D10-K)") (class "Default")
      (node (ref "C78") (pin "1") (pinfunction "1_1") (pintype "passive"))
      (node (ref "D10") (pin "1") (pinfunction "K_1") (pintype "passive"))
      (node (ref "R21") (pin "1") (pintype "passive"))
      (node (ref "R42") (pin "2") (pinfunction "2_2") (pintype "passive"))
      (node (ref "R69") (pin "2") (pintype "passive"))
      (node (ref "U10") (pin "3") (pinfunction "+_3") (pintype "passive"))
    )
    (net (code "44") (name "Net-(D11-K)") (class "Default")
      (node (ref "C79") (pin "1") (pinfunction "1_1") (pintype "passive"))
      (node (ref "D11") (pin "1") (pinfunction "K_1") (pintype "passive"))
      (node (ref "R24") (pin "1") (pintype "passive"))
      (node (ref "R42") (pin "1") (pinfunction "1_1") (pintype "passive"))
      (node (ref "R70") (pin "2") (pintype "passive"))
      (node (ref "U10") (pin "5") (pinfunction "+_5") (pintype "passive"))
    )
    (net (code "45") (name "Net-(D12-K)") (class "Default")
      (node (ref "C80") (pin "1") (pinfunction "1_1") (pintype "passive"))
      (node (ref "D12") (pin "1") (pinfunction "K_1") (pintype "passive"))
      (node (ref "R26") (pin "1") (pintype "passive"))
      (node (ref "R51") (pin "2") (pinfunction "2_2") (pintype "passive"))
      (node (ref "R71") (pin "2") (pintype "passive"))
      (node (ref "U11") (pin "3") (pinfunction "+_3") (pintype "passive"))
    )
    (net (code "46") (name "Net-(D13-K)") (class "Default")
      (node (ref "C81") (pin "1") (pinfunction "1_1") (pintype "passive"))
      (node (ref "D13") (pin "1") (pinfunction "K_1") (pintype "passive"))
      (node (ref "R27") (pin "1") (pintype "passive"))
      (node (ref "R51") (pin "1") (pinfunction "1_1") (pintype "passive"))
      (node (ref "R72") (pin "2") (pintype "passive"))
      (node (ref "U11") (pin "5") (pinfunction "+_5") (pintype "passive"))
    )
    (net (code "47") (name "VCC") (class "Default")
      (node (ref "C50") (pin "1") (pinfunction "1_1") (pintype "passive"))
      (node (ref "C51") (pin "1") (pinfunction "1_1") (pintype "passive"))
      (node (ref "C52") (pin "1") (pinfunction "1_1") (pintype "passive"))
      (node (ref "C53") (pin "1") (pinfunction "1_1") (pintype "passive"))
      (node (ref "C54") (pin "1") (pinfunction "1_1") (pintype "passive"))
      (node (ref "C55") (pin "1") (pinfunction "1_1") (pintype "passive"))
      (node (ref "C56") (pin "1") (pinfunction "1_1") (pintype "passive"))
      (node (ref "C57") (pin "1") (pinfunction "1_1") (pintype "passive"))
      (node (ref "U10") (pin "8") (pintype "passive"))
      (node (ref "U11") (pin "8") (pintype "passive"))
      (node (ref "U15") (pin "3") (pinfunction "VS+_3") (pintype "power_in"))
      (node (ref "U16") (pin "3") (pinfunction "VS+_3") (pintype "power_in"))
      (node (ref "U17") (pin "3") (pinfunction "VS+_3") (pintype "power_in"))
      (node (ref "U18") (pin "3") (pinfunction "VS+_3") (pintype "power_in"))
      (node (ref "U7") (pin "8") (pintype "passive"))
      (node (ref "U9") (pin "8") (pintype "passive"))
    )
    (net (code "48") (name "VCC-") (class "Default")
      (node (ref "C60") (pin "2") (pinfunction "2_2") (pintype "passive"))
      (node (ref "C61") (pin "2") (pinfunction "2_2") (pintype "passive"))
      (node (ref "C62") (pin "2") (pinfunction "2_2") (pintype "passive"))
      (node (ref "C63") (pin "2") (pinfunction "2_2") (pintype "passive"))
      (node (ref "U10") (pin "4") (pintype "passive"))
      (node (ref "U11") (pin "4") (pintype "passive"))
      (node (ref "U7") (pin "4") (pintype "passive"))
      (node (ref "U9") (pin "4") (pintype "passive"))
    )
    (net (code "49") (name "VCOM") (class "Default")
      (node (ref "C46") (pin "1") (pinfunction "1_1") (pintype "passive"))
      (node (ref "C47") (pin "1") (pinfunction "1_1") (pintype "passive"))
      (node (ref "C48") (pin "1") (pinfunction "1_1") (pintype "passive"))
      (node (ref "C49") (pin "1") (pinfunction "1_1") (pintype "passive"))
      (node (ref "U15") (pin "2") (pinfunction "VOCM_2") (pintype "input"))
      (node (ref "U16") (pin "2") (pinfunction "VOCM_2") (pintype "input"))
      (node (ref "U17") (pin "2") (pinfunction "VOCM_2") (pintype "input"))
      (node (ref "U18") (pin "2") (pinfunction "VOCM_2") (pintype "input"))
    )
    (net (code "50") (name "unconnected-(U15-~{PD}-Pad7)") (class "Default")
      (node (ref "U15") (pin "7") (pinfunction "~{PD}_7") (pintype "input+no_connect"))
    )
    (net (code "51") (name "unconnected-(U16-~{PD}-Pad7)") (class "Default")
      (node (ref "U16") (pin "7") (pinfunction "~{PD}_7") (pintype "input+no_connect"))
    )
    (net (code "52") (name "unconnected-(U17-~{PD}-Pad7)") (class "Default")
      (node (ref "U17") (pin "7") (pinfunction "~{PD}_7") (pintype "input+no_connect"))
    )
    (net (code "53") (name "unconnected-(U18-~{PD}-Pad7)") (class "Default")
      (node (ref "U18") (pin "7") (pinfunction "~{PD}_7") (pintype "input+no_connect"))
    )
  )
)
